# DCshieldV0_42.net
KiCad netlist of a schematic drawn in EAGLE
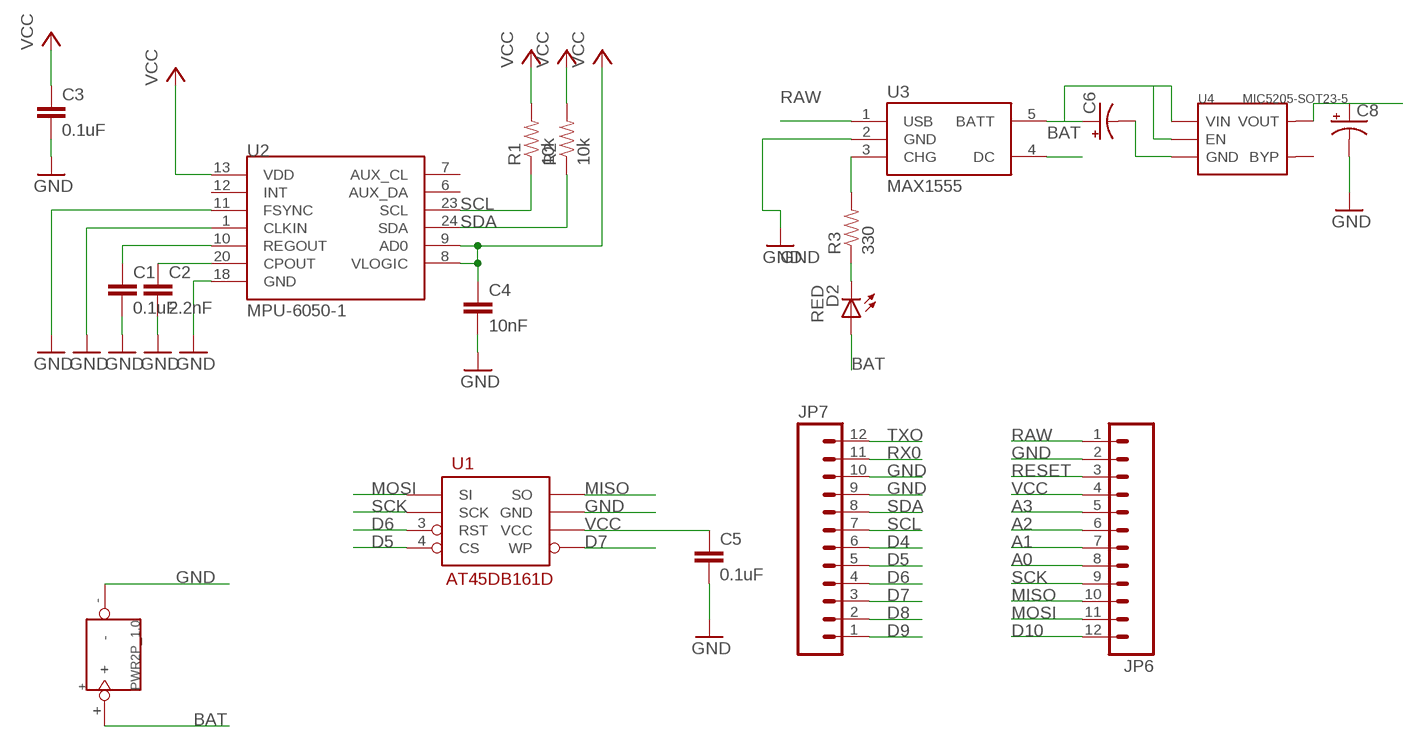
[diagram p0: schematic, sheet 1]

(export (version "E")
  (design (tool "Eeschema 10.0.6"))
  (components
    (comp (ref "+")
      (value "PWR2P_1.0")
      (footprint "eagle-import:PWR2P_1.0")
      (libsource (lib "eagle-import") (part "PWR2P_1.0"))
    )
    (comp (ref "C1")
      (value "0.1uF")
      (footprint "eagle-import:0402-CAP")
      (libsource (lib "eagle-import") (part "CAP0402-CAP"))
    )
    (comp (ref "C2")
      (value "2.2nF")
      (footprint "eagle-import:0402-CAP")
      (libsource (lib "eagle-import") (part "CAP0402-CAP"))
    )
    (comp (ref "C3")
      (value "0.1uF")
      (footprint "eagle-import:0402-CAP")
      (libsource (lib "eagle-import") (part "CAP0402-CAP"))
    )
    (comp (ref "C4")
      (value "10nF")
      (footprint "eagle-import:0402-CAP")
      (libsource (lib "eagle-import") (part "CAP0402-CAP"))
    )
    (comp (ref "C5")
      (value "0.1uF")
      (footprint "eagle-import:0402-CAP")
      (libsource (lib "eagle-import") (part "CAP0402-CAP"))
    )
    (comp (ref "C6")
      (value "CAP_POL1206")
      (footprint "eagle-import:EIA3216")
      (libsource (lib "eagle-import") (part "CAP_POL1206"))
    )
    (comp (ref "C8")
      (value "CAP_POL1206")
      (footprint "eagle-import:EIA3216")
      (libsource (lib "eagle-import") (part "CAP_POL1206"))
    )
    (comp (ref "D2")
      (value "RED")
      (footprint "eagle-import:LED-0603")
      (libsource (lib "eagle-import") (part "LED-RED0603"))
    )
    (comp (ref "JP6")
      (value "M12PTH")
      (footprint "eagle-import:1X12")
      (libsource (lib "eagle-import") (part "M12PTH"))
    )
    (comp (ref "JP7")
      (value "M12PTH")
      (footprint "eagle-import:1X12")
      (libsource (lib "eagle-import") (part "M12PTH"))
    )
    (comp (ref "R1")
      (value "10k")
      (footprint "eagle-import:0402-RES")
      (libsource (lib "eagle-import") (part "RESISTOR0402-RES"))
    )
    (comp (ref "R2")
      (value "10k")
      (footprint "eagle-import:0402-RES")
      (libsource (lib "eagle-import") (part "RESISTOR0402-RES"))
    )
    (comp (ref "R3")
      (value "330")
      (footprint "eagle-import:0402-RES")
      (libsource (lib "eagle-import") (part "RESISTOR0402-RES"))
    )
    (comp (ref "U1")
      (value "AT45DB161D")
      (footprint "eagle-import:SO08-EIAJ")
      (libsource (lib "eagle-import") (part "AT45DB161D"))
    )
    (comp (ref "U2")
      (value "MPU-6050-1")
      (footprint "eagle-import:QFN-24-4MM2")
      (libsource (lib "eagle-import") (part "MPU-6050-1"))
    )
    (comp (ref "U3")
      (value "MAX1555")
      (footprint "eagle-import:SOT23-5")
      (libsource (lib "eagle-import") (part "MAX1555"))
    )
    (comp (ref "U4")
      (value "MIC5205-SOT23-5")
      (footprint "eagle-import:SOT23-5")
      (libsource (lib "eagle-import") (part "MIC5205-SOT23-5"))
    )
  )
  (nets
    (net (code "1") (name "/A0") (class "Default")
      (node (ref "JP6") (pin "8") (pinfunction "8_8") (pintype "passive"))
    )
    (net (code "2") (name "/A1") (class "Default")
      (node (ref "JP6") (pin "7") (pinfunction "7_7") (pintype "passive"))
    )
    (net (code "3") (name "/A2") (class "Default")
      (node (ref "JP6") (pin "6") (pinfunction "6_6") (pintype "passive"))
    )
    (net (code "4") (name "/A3") (class "Default")
      (node (ref "JP6") (pin "5") (pinfunction "5_5") (pintype "passive"))
    )
    (net (code "5") (name "/BAT") (class "Default")
      (node (ref "+") (pin "+") (pinfunction "+_+") (pintype "bidirectional"))
      (node (ref "C6") (pin "A") (pinfunction "+_A") (pintype "passive"))
      (node (ref "D2") (pin "A") (pinfunction "A_A") (pintype "passive"))
      (node (ref "U3") (pin "5") (pinfunction "BATT_5") (pintype "bidirectional"))
      (node (ref "U4") (pin "1") (pinfunction "VIN_1") (pintype "bidirectional"))
      (node (ref "U4") (pin "3") (pinfunction "EN_3") (pintype "bidirectional"))
    )
    (net (code "6") (name "/D4") (class "Default")
      (node (ref "JP7") (pin "6") (pinfunction "6_6") (pintype "passive"))
    )
    (net (code "7") (name "/D5") (class "Default")
      (node (ref "JP7") (pin "5") (pinfunction "5_5") (pintype "passive"))
      (node (ref "U1") (pin "4") (pinfunction "CS_4") (pintype "bidirectional"))
    )
    (net (code "8") (name "/D6") (class "Default")
      (node (ref "JP7") (pin "4") (pinfunction "4_4") (pintype "passive"))
      (node (ref "U1") (pin "3") (pinfunction "RST_3") (pintype "bidirectional"))
    )
    (net (code "9") (name "/D7") (class "Default")
      (node (ref "JP7") (pin "3") (pinfunction "3_3") (pintype "passive"))
      (node (ref "U1") (pin "5") (pinfunction "WP_5") (pintype "bidirectional"))
    )
    (net (code "10") (name "/D8") (class "Default")
      (node (ref "JP7") (pin "2") (pinfunction "2_2") (pintype "passive"))
    )
    (net (code "11") (name "/D9") (class "Default")
      (node (ref "JP7") (pin "1") (pinfunction "1_1") (pintype "passive"))
    )
    (net (code "12") (name "/D10") (class "Default")
      (node (ref "JP6") (pin "12") (pinfunction "12_12") (pintype "passive"))
    )
    (net (code "13") (name "/MISO") (class "Default")
      (node (ref "JP6") (pin "10") (pinfunction "10_10") (pintype "passive"))
      (node (ref "U1") (pin "8") (pinfunction "SO_8") (pintype "bidirectional"))
    )
    (net (code "14") (name "/MOSI") (class "Default")
      (node (ref "JP6") (pin "11") (pinfunction "11_11") (pintype "passive"))
      (node (ref "U1") (pin "1") (pinfunction "SI_1") (pintype "bidirectional"))
    )
    (net (code "15") (name "/RAW") (class "Default")
      (node (ref "JP6") (pin "1") (pinfunction "1_1") (pintype "passive"))
      (node (ref "U3") (pin "1") (pinfunction "USB_1") (pintype "bidirectional"))
      (node (ref "U3") (pin "4") (pinfunction "DC_4") (pintype "bidirectional"))
    )
    (net (code "16") (name "/RESET") (class "Default")
      (node (ref "JP6") (pin "3") (pinfunction "3_3") (pintype "passive"))
    )
    (net (code "17") (name "/RX0") (class "Default")
      (node (ref "JP7") (pin "11") (pinfunction "11_11") (pintype "passive"))
    )
    (net (code "18") (name "/SCK") (class "Default")
      (node (ref "JP6") (pin "9") (pinfunction "9_9") (pintype "passive"))
      (node (ref "U1") (pin "2") (pinfunction "SCK_2") (pintype "bidirectional"))
    )
    (net (code "19") (name "/SCL") (class "Default")
      (node (ref "JP7") (pin "7") (pinfunction "7_7") (pintype "passive"))
      (node (ref "R1") (pin "1") (pinfunction "1_1") (pintype "passive"))
      (node (ref "U2") (pin "23") (pinfunction "SCL_23") (pintype "bidirectional"))
    )
    (net (code "20") (name "/SDA") (class "Default")
      (node (ref "JP7") (pin "8") (pinfunction "8_8") (pintype "passive"))
      (node (ref "R2") (pin "1") (pinfunction "1_1") (pintype "passive"))
      (node (ref "U2") (pin "24") (pinfunction "SDA_24") (pintype "bidirectional"))
    )
    (net (code "21") (name "/TXO") (class "Default")
      (node (ref "JP7") (pin "12") (pinfunction "12_12") (pintype "passive"))
    )
    (net (code "22") (name "GND") (class "Default")
      (node (ref "+") (pin "-") (pinfunction "-_-") (pintype "bidirectional"))
      (node (ref "C1") (pin "2") (pinfunction "2_2") (pintype "passive"))
      (node (ref "C2") (pin "2") (pinfunction "2_2") (pintype "passive"))
      (node (ref "C3") (pin "2") (pinfunction "2_2") (pintype "passive"))
      (node (ref "C4") (pin "2") (pinfunction "2_2") (pintype "passive"))
      (node (ref "C5") (pin "2") (pinfunction "2_2") (pintype "passive"))
      (node (ref "C6") (pin "C") (pinfunction "-_C") (pintype "passive"))
      (node (ref "C8") (pin "C") (pinfunction "-_C") (pintype "passive"))
      (node (ref "JP6") (pin "2") (pinfunction "2_2") (pintype "passive"))
      (node (ref "JP7") (pin "10") (pinfunction "10_10") (pintype "passive"))
      (node (ref "JP7") (pin "9") (pinfunction "9_9") (pintype "passive"))
      (node (ref "U1") (pin "7") (pinfunction "GND_7") (pintype "bidirectional"))
      (node (ref "U2") (pin "1") (pinfunction "CLKIN_1") (pintype "bidirectional"))
      (node (ref "U2") (pin "11") (pinfunction "FSYNC_11") (pintype "bidirectional"))
      (node (ref "U2") (pin "18") (pinfunction "GND_18") (pintype "bidirectional"))
      (node (ref "U3") (pin "2") (pinfunction "GND_2") (pintype "bidirectional"))
      (node (ref "U4") (pin "2") (pinfunction "GND_2") (pintype "bidirectional"))
    )
    (net (code "23") (name "Net-(D2-PadC)") (class "Default")
      (node (ref "D2") (pin "C") (pinfunction "C_C") (pintype "passive"))
      (node (ref "R3") (pin "1") (pinfunction "1_1") (pintype "passive"))
    )
    (net (code "24") (name "Net-(U2-CPOUT)") (class "Default")
      (node (ref "C2") (pin "1") (pinfunction "1_1") (pintype "passive"))
      (node (ref "U2") (pin "20") (pinfunction "CPOUT_20") (pintype "bidirectional"))
    )
    (net (code "25") (name "Net-(U2-REGOUT)") (class "Default")
      (node (ref "C1") (pin "1") (pinfunction "1_1") (pintype "passive"))
      (node (ref "U2") (pin "10") (pinfunction "REGOUT_10") (pintype "bidirectional"))
    )
    (net (code "26") (name "Net-(U3-CHG)") (class "Default")
      (node (ref "R3") (pin "2") (pinfunction "2_2") (pintype "passive"))
      (node (ref "U3") (pin "3") (pinfunction "CHG_3") (pintype "bidirectional"))
    )
    (net (code "27") (name "VCC") (class "Default")
      (node (ref "C3") (pin "1") (pinfunction "1_1") (pintype "passive"))
      (node (ref "C4") (pin "1") (pinfunction "1_1") (pintype "passive"))
      (node (ref "C5") (pin "1") (pinfunction "1_1") (pintype "passive"))
      (node (ref "C8") (pin "A") (pinfunction "+_A") (pintype "passive"))
      (node (ref "JP6") (pin "4") (pinfunction "4_4") (pintype "passive"))
      (node (ref "R1") (pin "2") (pinfunction "2_2") (pintype "passive"))
      (node (ref "R2") (pin "2") (pinfunction "2_2") (pintype "passive"))
      (node (ref "U1") (pin "6") (pinfunction "VCC_6") (pintype "bidirectional"))
      (node (ref "U2") (pin "13") (pinfunction "VDD_13") (pintype "bidirectional"))
      (node (ref "U2") (pin "8") (pinfunction "VLOGIC_8") (pintype "bidirectional"))
      (node (ref "U2") (pin "9") (pinfunction "AD0_9") (pintype "bidirectional"))
      (node (ref "U4") (pin "5") (pinfunction "VOUT_5") (pintype "bidirectional"))
    )
    (net (code "28") (name "unconnected-(U2-AUX_CL-Pad7)") (class "Default")
      (node (ref "U2") (pin "7") (pinfunction "AUX_CL_7") (pintype "bidirectional"))
    )
    (net (code "29") (name "unconnected-(U2-AUX_DA-Pad6)") (class "Default")
      (node (ref "U2") (pin "6") (pinfunction "AUX_DA_6") (pintype "bidirectional"))
    )
    (net (code "30") (name "unconnected-(U2-INT-Pad12)") (class "Default")
      (node (ref "U2") (pin "12") (pinfunction "INT_12") (pintype "bidirectional"))
    )
    (net (code "31") (name "unconnected-(U4-BYP-Pad4)") (class "Default")
      (node (ref "U4") (pin "4") (pinfunction "BYP_4") (pintype "bidirectional"))
    )
  )
)
